# powerBoard.net
KiCad netlist of a schematic drawn in EAGLE
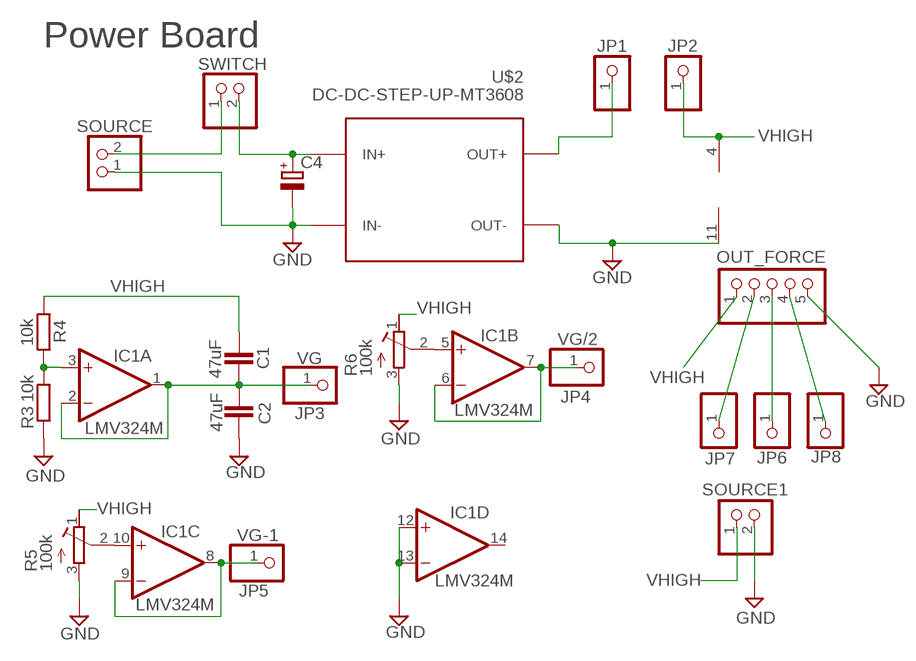
[diagram p0: schematic, sheet 1]

(export (version "E")
  (design (tool "Eeschema 10.0.6"))
  (components
    (comp (ref "C1")
      (value "47uF")
      (footprint "eagle-import:C0805")
      (libsource (lib "eagle-import") (part "C-EUC0805"))
    )
    (comp (ref "C2")
      (value "47uF")
      (footprint "eagle-import:C0805")
      (libsource (lib "eagle-import") (part "C-EUC0805"))
    )
    (comp (ref "C4")
      (value "CPOL-EUE2.5-7")
      (footprint "eagle-import:E2,5-7")
      (libsource (lib "eagle-import") (part "CPOL-EUE2.5-7"))
    )
    (comp (ref "IC1")
      (value "LMV324M")
      (footprint "eagle-import:SO14")
      (libsource (lib "eagle-import") (part "LMV324?M"))
    )
    (comp (ref "JP1")
      (value "PINHD-1X1")
      (footprint "eagle-import:1X01")
      (libsource (lib "eagle-import") (part "PINHD-1X1"))
    )
    (comp (ref "JP2")
      (value "PINHD-1X1")
      (footprint "eagle-import:1X01")
      (libsource (lib "eagle-import") (part "PINHD-1X1"))
    )
    (comp (ref "JP3")
      (value "PINHD-1X1")
      (footprint "eagle-import:1X01")
      (libsource (lib "eagle-import") (part "PINHD-1X1"))
    )
    (comp (ref "JP4")
      (value "PINHD-1X1")
      (footprint "eagle-import:1X01")
      (libsource (lib "eagle-import") (part "PINHD-1X1"))
    )
    (comp (ref "JP5")
      (value "PINHD-1X1")
      (footprint "eagle-import:1X01")
      (libsource (lib "eagle-import") (part "PINHD-1X1"))
    )
    (comp (ref "JP6")
      (value "PINHD-1X1")
      (footprint "eagle-import:1X01")
      (libsource (lib "eagle-import") (part "PINHD-1X1"))
    )
    (comp (ref "JP7")
      (value "PINHD-1X1")
      (footprint "eagle-import:1X01")
      (libsource (lib "eagle-import") (part "PINHD-1X1"))
    )
    (comp (ref "JP8")
      (value "PINHD-1X1")
      (footprint "eagle-import:1X01")
      (libsource (lib "eagle-import") (part "PINHD-1X1"))
    )
    (comp (ref "OUT_FORCE")
      (value "PINHD-1X5")
      (footprint "eagle-import:1X05")
      (libsource (lib "eagle-import") (part "PINHD-1X5"))
    )
    (comp (ref "R3")
      (value "10k")
      (footprint "eagle-import:R0805")
      (libsource (lib "eagle-import") (part "R-EU_R0805"))
    )
    (comp (ref "R4")
      (value "10k")
      (footprint "eagle-import:R0805")
      (libsource (lib "eagle-import") (part "R-EU_R0805"))
    )
    (comp (ref "R5")
      (value "100k")
      (footprint "eagle-import:RTRIM3006P")
      (libsource (lib "eagle-import") (part "R-TRIMM3006P"))
    )
    (comp (ref "R6")
      (value "100k")
      (footprint "eagle-import:RTRIM3006P")
      (libsource (lib "eagle-import") (part "R-TRIMM3006P"))
    )
    (comp (ref "SOURCE")
      (value "PINHD-1X2")
      (footprint "eagle-import:1X02")
      (libsource (lib "eagle-import") (part "PINHD-1X2"))
    )
    (comp (ref "SOURCE1")
      (value "PINHD-1X2")
      (footprint "eagle-import:1X02")
      (libsource (lib "eagle-import") (part "PINHD-1X2"))
    )
    (comp (ref "SWITCH")
      (value "PINHD-1X2")
      (footprint "eagle-import:1X02")
      (libsource (lib "eagle-import") (part "PINHD-1X2"))
    )
    (comp (ref "U$2")
      (value "DC-DC-STEP-UP-MT3608")
      (footprint "eagle-import:DC-DC-STEP-UP-MT3608")
      (libsource (lib "eagle-import") (part "DC-DC-STEP-UP-MT3608"))
    )
  )
  (nets
    (net (code "1") (name "/VG") (class "Default")
      (node (ref "C1") (pin "2") (pinfunction "2_2") (pintype "passive"))
      (node (ref "C2") (pin "1") (pinfunction "1_1") (pintype "passive"))
      (node (ref "IC1") (pin "1") (pinfunction "OUT_1") (pintype "output"))
      (node (ref "IC1") (pin "2") (pinfunction "-IN_2") (pintype "input"))
      (node (ref "JP3") (pin "1") (pinfunction "1_1") (pintype "passive"))
    )
    (net (code "2") (name "/VG-1") (class "Default")
      (node (ref "IC1") (pin "8") (pinfunction "OUT_8") (pintype "output"))
      (node (ref "IC1") (pin "9") (pinfunction "-IN_9") (pintype "input"))
      (node (ref "JP5") (pin "1") (pinfunction "1_1") (pintype "passive"))
    )
    (net (code "3") (name "/VG{slash}2") (class "Default")
      (node (ref "IC1") (pin "6") (pinfunction "-IN_6") (pintype "input"))
      (node (ref "IC1") (pin "7") (pinfunction "OUT_7") (pintype "output"))
      (node (ref "JP4") (pin "1") (pinfunction "1_1") (pintype "passive"))
    )
    (net (code "4") (name "/VHIGH") (class "Default")
      (node (ref "C1") (pin "1") (pinfunction "1_1") (pintype "passive"))
      (node (ref "IC1") (pin "4") (pinfunction "V+_4") (pintype "power_in"))
      (node (ref "JP2") (pin "1") (pinfunction "1_1") (pintype "passive"))
      (node (ref "OUT_FORCE") (pin "1") (pinfunction "1_1") (pintype "passive"))
      (node (ref "R4") (pin "1") (pinfunction "1_1") (pintype "passive"))
      (node (ref "R5") (pin "1") (pinfunction "E_1") (pintype "passive"))
      (node (ref "R6") (pin "1") (pinfunction "E_1") (pintype "passive"))
      (node (ref "SOURCE1") (pin "1") (pinfunction "1_1") (pintype "passive"))
    )
    (net (code "5") (name "GND") (class "Default")
      (node (ref "C2") (pin "2") (pinfunction "2_2") (pintype "passive"))
      (node (ref "C4") (pin "-") (pinfunction "-_-") (pintype "passive"))
      (node (ref "IC1") (pin "11") (pinfunction "V-_11") (pintype "power_in"))
      (node (ref "IC1") (pin "12") (pinfunction "+IN_12") (pintype "input"))
      (node (ref "IC1") (pin "13") (pinfunction "-IN_13") (pintype "input"))
      (node (ref "OUT_FORCE") (pin "5") (pinfunction "5_5") (pintype "passive"))
      (node (ref "R3") (pin "1") (pinfunction "1_1") (pintype "passive"))
      (node (ref "R5") (pin "3") (pinfunction "A_3") (pintype "passive"))
      (node (ref "R6") (pin "3") (pinfunction "A_3") (pintype "passive"))
      (node (ref "SOURCE") (pin "1") (pinfunction "1_1") (pintype "passive"))
      (node (ref "SOURCE1") (pin "2") (pinfunction "2_2") (pintype "passive"))
      (node (ref "U$2") (pin "IN-") (pinfunction "IN-_IN-") (pintype "bidirectional"))
      (node (ref "U$2") (pin "OUT-") (pinfunction "OUT-_OUT-") (pintype "bidirectional"))
    )
    (net (code "6") (name "Net-(C4-Pad+)") (class "Default")
      (node (ref "C4") (pin "+") (pinfunction "+_+") (pintype "passive"))
      (node (ref "SWITCH") (pin "2") (pinfunction "2_2") (pintype "passive"))
      (node (ref "U$2") (pin "IN+") (pinfunction "IN+_IN+") (pintype "bidirectional"))
    )
    (net (code "7") (name "Net-(IC1A-+IN)") (class "Default")
      (node (ref "IC1") (pin "3") (pinfunction "+IN_3") (pintype "input"))
      (node (ref "R3") (pin "2") (pinfunction "2_2") (pintype "passive"))
      (node (ref "R4") (pin "2") (pinfunction "2_2") (pintype "passive"))
    )
    (net (code "8") (name "Net-(IC1B-+IN)") (class "Default")
      (node (ref "IC1") (pin "5") (pinfunction "+IN_5") (pintype "input"))
      (node (ref "R6") (pin "2") (pinfunction "S_2") (pintype "passive"))
    )
    (net (code "9") (name "Net-(IC1C-+IN)") (class "Default")
      (node (ref "IC1") (pin "10") (pinfunction "+IN_10") (pintype "input"))
      (node (ref "R5") (pin "2") (pinfunction "S_2") (pintype "passive"))
    )
    (net (code "10") (name "Net-(JP1-Pad1)") (class "Default")
      (node (ref "JP1") (pin "1") (pinfunction "1_1") (pintype "passive"))
      (node (ref "U$2") (pin "OUT+") (pinfunction "OUT+_OUT+") (pintype "bidirectional"))
    )
    (net (code "11") (name "Net-(JP6-Pad1)") (class "Default")
      (node (ref "JP6") (pin "1") (pinfunction "1_1") (pintype "passive"))
      (node (ref "OUT_FORCE") (pin "3") (pinfunction "3_3") (pintype "passive"))
    )
    (net (code "12") (name "Net-(JP7-Pad1)") (class "Default")
      (node (ref "JP7") (pin "1") (pinfunction "1_1") (pintype "passive"))
      (node (ref "OUT_FORCE") (pin "2") (pinfunction "2_2") (pintype "passive"))
    )
    (net (code "13") (name "Net-(JP8-Pad1)") (class "Default")
      (node (ref "JP8") (pin "1") (pinfunction "1_1") (pintype "passive"))
      (node (ref "OUT_FORCE") (pin "4") (pinfunction "4_4") (pintype "passive"))
    )
    (net (code "14") (name "Net-(SOURCE-Pad2)") (class "Default")
      (node (ref "SOURCE") (pin "2") (pinfunction "2_2") (pintype "passive"))
      (node (ref "SWITCH") (pin "1") (pinfunction "1_1") (pintype "passive"))
    )
    (net (code "15") (name "unconnected-(IC1D-OUT-Pad14)") (class "Default")
      (node (ref "IC1") (pin "14") (pinfunction "OUT_14") (pintype "output"))
    )
  )
)
